# Display.net
KiCad netlist of a schematic drawn in Altium Designer
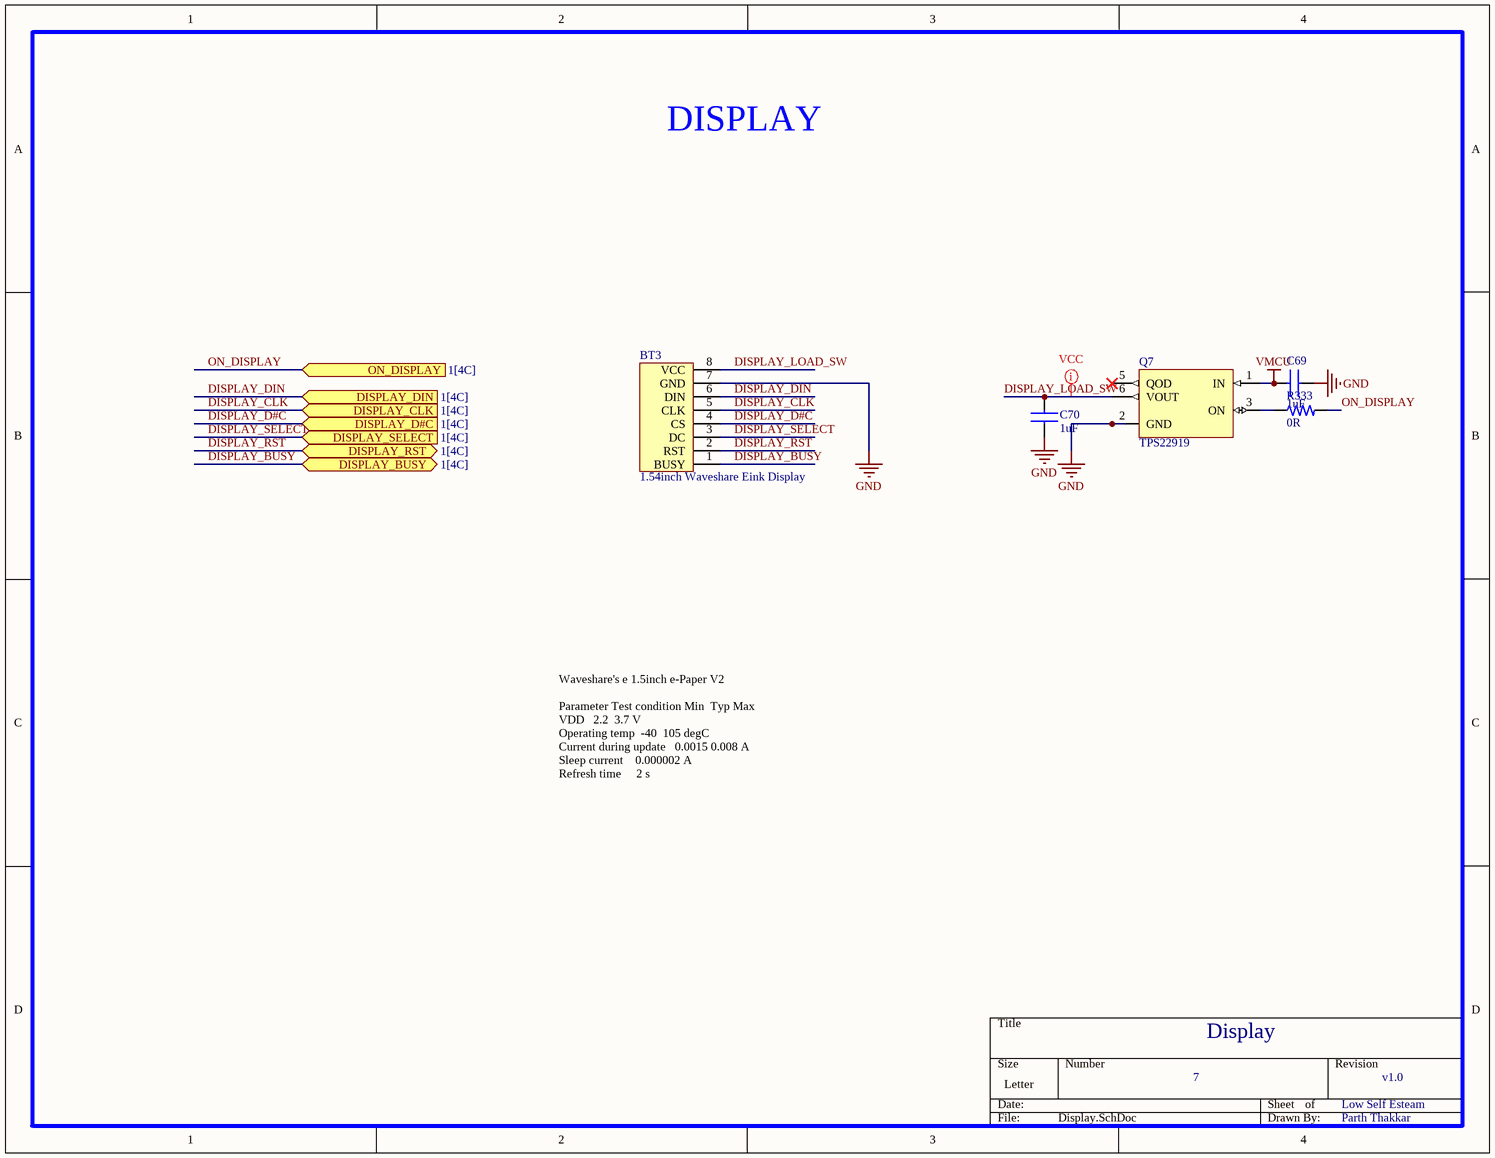
[diagram p0: Display.SchDoc]

(export (version "E")
  (design (tool "Eeschema 10.0.6"))
  (components
    (comp (ref "BT3")
      (value "1.54inch Waveshare Eink Display")
      (footprint "1.54inch waveshare eink")
      (libsource (lib "Keyboard_parts") (part "1.54inch Waveshare Eink Display"))
    )
    (comp (ref "C69")
      (value "1uF")
      (footprint "Capacitor 0603")
      (fields
        (field (name "MANUFACTURER") "Murata")
        (field (name "MANUFACTURER PART NUMBER") "GRM188R61A105KA61D")
        (field (name "Comment") "CAP 1uF 10V 0603")
      )
      (libsource (lib "Keyboard_parts") (part "CAP 1uF 10V 0603"))
    )
    (comp (ref "C70")
      (value "1uF")
      (footprint "CAPACITOR 0805")
      (description "Multilayer Ceramic Capacitor, 1 uF, 10 V, ± 20%, X5R, 0201 [0603 Metric]")
      (fields
        (field (name "MANUFACTURER") "Murata")
        (field (name "MANUFACTURER PART NUMBER") "GRM033R61A105ME15D")
      )
      (libsource (lib "Keyboard_parts") (part "CAP 47uF 10V 0805"))
    )
    (comp (ref "Q7")
      (value "TPS22919")
      (footprint "TPS22919DCKR - Load SW")
      (description "Buffer/Inverter Based Peripheral Driver, 3A, PDSO6")
      (fields
        (field (name "MANUFACTURER") "Texas Instruments")
        (field (name "MANUFACTURER PART NUMBER") "TPS22919DCKT")
      )
      (libsource (lib "Keyboard_parts") (part "TPS22919"))
    )
    (comp (ref "R333")
      (value "0R")
      (footprint "Resistor 0402")
      (description "Metal Glaze/thick Film, 0.0625W, 0ohm, Surface Mount, 0402")
      (fields
        (field (name "MANUFACTURER") "Yageo")
        (field (name "MANUFACTURER PART NUMBER") "RC0402JR-070RL")
      )
      (libsource (lib "Keyboard_parts") (part "RES 0R 0402"))
    )
  )
  (nets
    (net (code "1") (name "/DISPLAY_BUSY") (class "Default")
      (node (ref "BT3") (pin "1") (pinfunction "BUSY_1") (pintype "passive"))
    )
    (net (code "2") (name "/DISPLAY_CLK") (class "Default")
      (node (ref "BT3") (pin "5") (pinfunction "CLK_5") (pintype "passive"))
    )
    (net (code "3") (name "/DISPLAY_D#C") (class "Default")
      (node (ref "BT3") (pin "4") (pinfunction "CS_4") (pintype "passive"))
    )
    (net (code "4") (name "/DISPLAY_DIN") (class "Default")
      (node (ref "BT3") (pin "6") (pinfunction "DIN_6") (pintype "passive"))
    )
    (net (code "5") (name "/DISPLAY_LOAD_SW") (class "Default")
      (node (ref "BT3") (pin "8") (pinfunction "VCC_8") (pintype "passive"))
      (node (ref "C70") (pin "1") (pinfunction "1_1") (pintype "passive"))
      (node (ref "Q7") (pin "6") (pinfunction "VOUT_6") (pintype "output"))
    )
    (net (code "6") (name "/DISPLAY_RST") (class "Default")
      (node (ref "BT3") (pin "2") (pinfunction "RST_2") (pintype "passive"))
    )
    (net (code "7") (name "/DISPLAY_SELECT") (class "Default")
      (node (ref "BT3") (pin "3") (pinfunction "DC_3") (pintype "passive"))
    )
    (net (code "8") (name "/ON_DISPLAY") (class "Default")
      (node (ref "R333") (pin "2") (pinfunction "2_2") (pintype "passive"))
    )
    (net (code "9") (name "GND") (class "Default")
      (node (ref "BT3") (pin "7") (pinfunction "GND_7") (pintype "passive"))
      (node (ref "C69") (pin "2") (pinfunction "2_2") (pintype "passive"))
      (node (ref "C70") (pin "2") (pinfunction "2_2") (pintype "passive"))
      (node (ref "Q7") (pin "2") (pinfunction "GND_2") (pintype "power_in"))
    )
    (net (code "10") (name "Net-(Q7-ON)") (class "Default")
      (node (ref "Q7") (pin "3") (pinfunction "ON_3") (pintype "bidirectional"))
      (node (ref "R333") (pin "1") (pinfunction "1_1") (pintype "passive"))
    )
    (net (code "11") (name "VMCU") (class "Default")
      (node (ref "C69") (pin "1") (pinfunction "1_1") (pintype "passive"))
      (node (ref "Q7") (pin "1") (pinfunction "IN_1") (pintype "input"))
    )
    (net (code "12") (name "unconnected-(Q7-QOD-Pad5)") (class "Default")
      (node (ref "Q7") (pin "5") (pinfunction "QOD_5") (pintype "output+no_connect"))
    )
  )
)
